# humidor_controller_v35.net
KiCad netlist of a schematic drawn in EAGLE
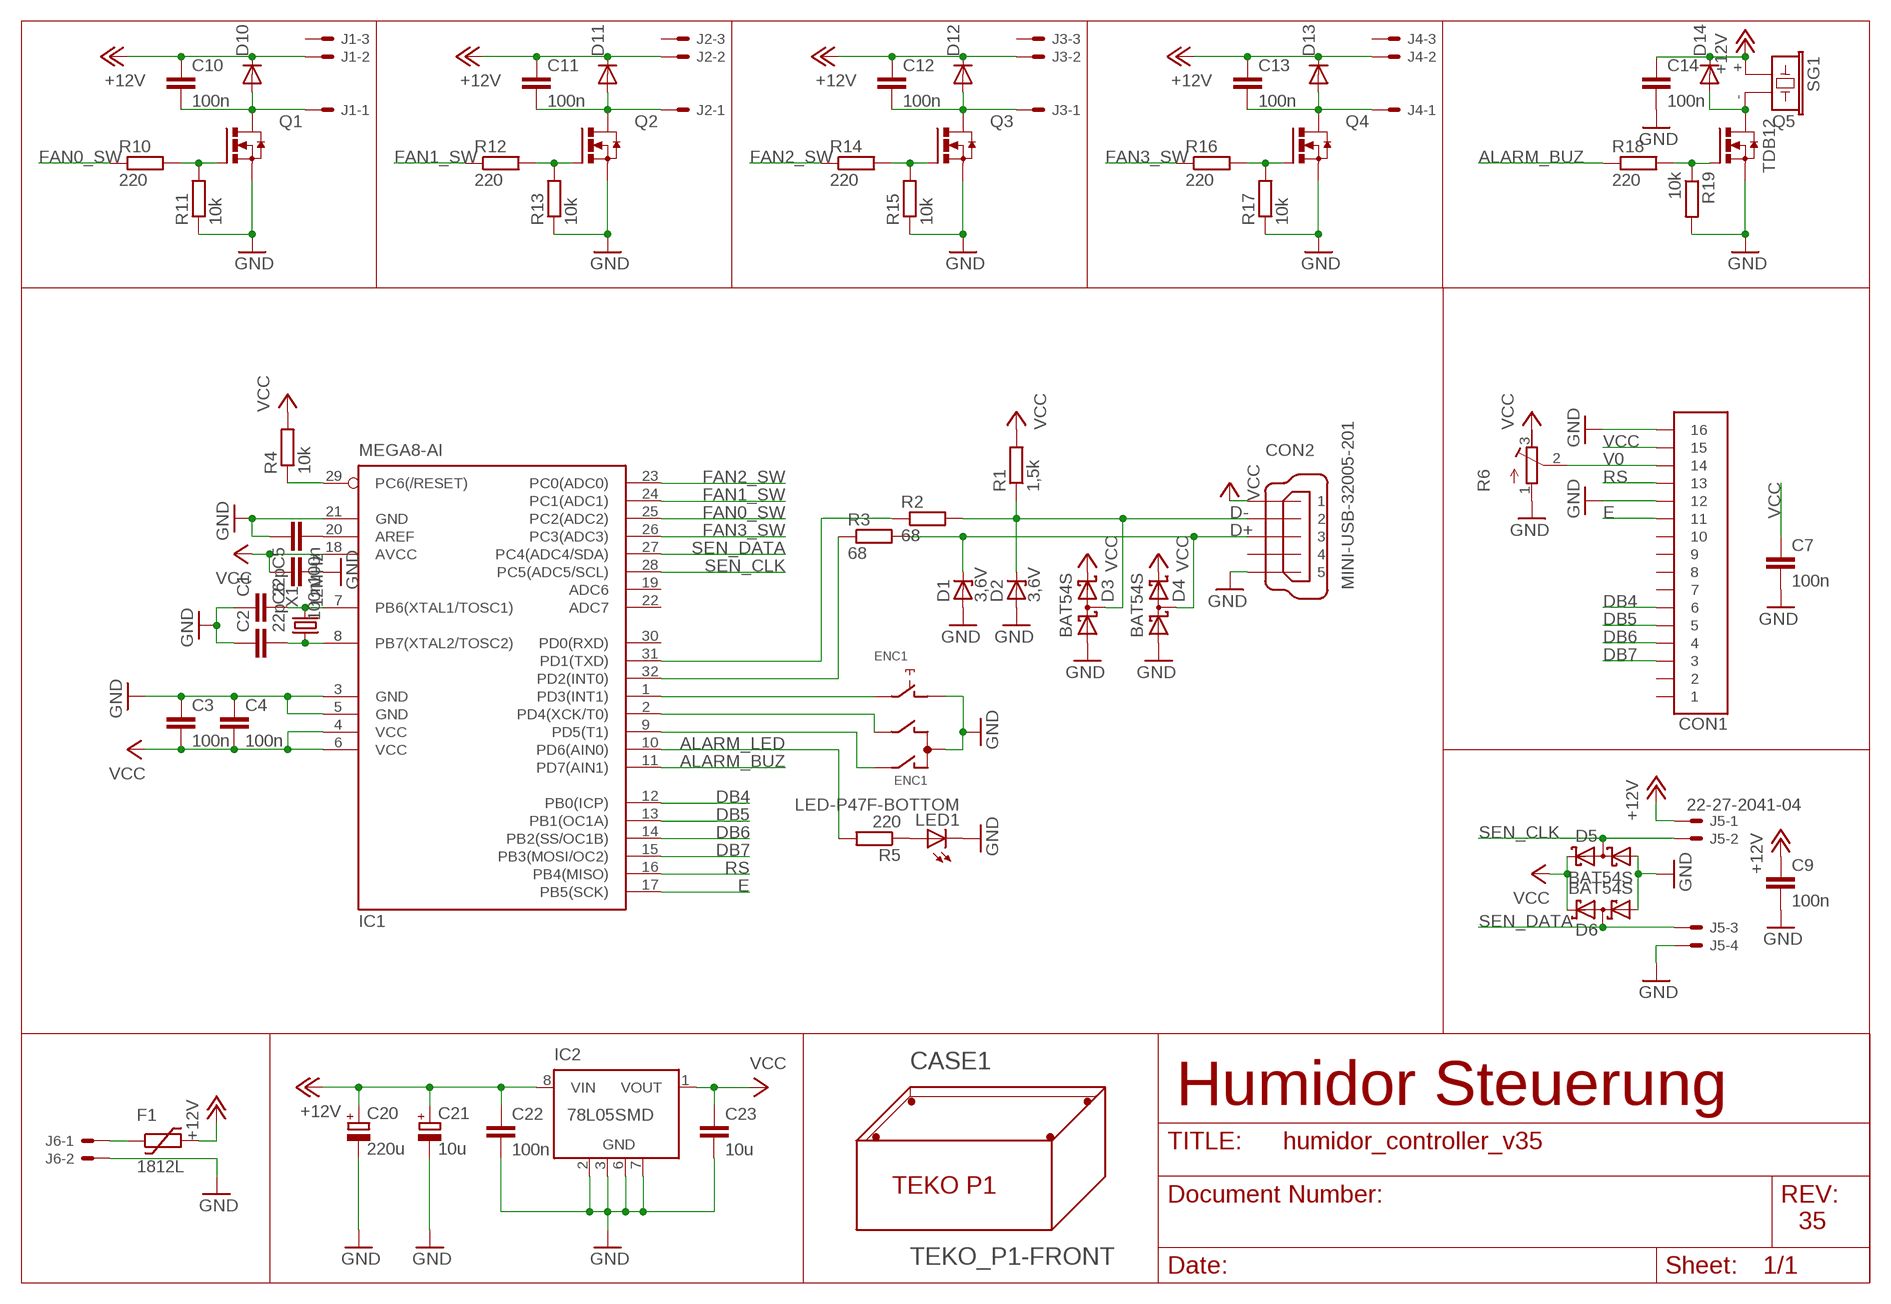
[diagram p0: schematic, sheet 1]

(export (version "E")
  (design (tool "Eeschema 10.0.6"))
  (components
    (comp (ref "C1")
      (value "22p")
      (footprint "eagle-import:C0805")
      (libsource (lib "eagle-import") (part "C-EUC0805"))
    )
    (comp (ref "C2")
      (value "22p")
      (footprint "eagle-import:C0805")
      (libsource (lib "eagle-import") (part "C-EUC0805"))
    )
    (comp (ref "C3")
      (value "100n")
      (footprint "eagle-import:C0805")
      (libsource (lib "eagle-import") (part "resistor_C-EUC0805"))
    )
    (comp (ref "C4")
      (value "100n")
      (footprint "eagle-import:C0805")
      (libsource (lib "eagle-import") (part "resistor_C-EUC0805"))
    )
    (comp (ref "C5")
      (value "100n")
      (footprint "eagle-import:C0805")
      (libsource (lib "eagle-import") (part "resistor_C-EUC0805"))
    )
    (comp (ref "C6")
      (value "100n")
      (footprint "eagle-import:C0805")
      (libsource (lib "eagle-import") (part "resistor_C-EUC0805"))
    )
    (comp (ref "C7")
      (value "100n")
      (footprint "eagle-import:C0805")
      (libsource (lib "eagle-import") (part "resistor_C-EUC0805"))
    )
    (comp (ref "C9")
      (value "100n")
      (footprint "eagle-import:C0805")
      (libsource (lib "eagle-import") (part "resistor_C-EUC0805"))
    )
    (comp (ref "C10")
      (value "100n")
      (footprint "eagle-import:C0805")
      (libsource (lib "eagle-import") (part "resistor_C-EUC0805"))
    )
    (comp (ref "C11")
      (value "100n")
      (footprint "eagle-import:C0805")
      (libsource (lib "eagle-import") (part "resistor_C-EUC0805"))
    )
    (comp (ref "C12")
      (value "100n")
      (footprint "eagle-import:C0805")
      (libsource (lib "eagle-import") (part "resistor_C-EUC0805"))
    )
    (comp (ref "C13")
      (value "100n")
      (footprint "eagle-import:C0805")
      (libsource (lib "eagle-import") (part "resistor_C-EUC0805"))
    )
    (comp (ref "C14")
      (value "100n")
      (footprint "eagle-import:C0805")
      (libsource (lib "eagle-import") (part "resistor_C-EUC0805"))
    )
    (comp (ref "C20")
      (value "220u")
      (footprint "eagle-import:PANASONIC_G")
      (libsource (lib "eagle-import") (part "CPOL-EUG"))
    )
    (comp (ref "C21")
      (value "10u")
      (footprint "eagle-import:PANASONIC_B")
      (libsource (lib "eagle-import") (part "CPOL-EUB"))
    )
    (comp (ref "C22")
      (value "100n")
      (footprint "eagle-import:C0805")
      (libsource (lib "eagle-import") (part "C-EUC0805"))
    )
    (comp (ref "C23")
      (value "10u")
      (footprint "eagle-import:C0805")
      (libsource (lib "eagle-import") (part "C-EUC0805"))
    )
    (comp (ref "CASE1")
      (value "TEKO_P1-FRONT")
      (footprint "eagle-import:TEKO_P1_FRONT")
      (libsource (lib "eagle-import") (part "TEKO_P1-FRONT"))
    )
    (comp (ref "CON1")
      (value "52207-16")
      (footprint "eagle-import:52207-16")
      (libsource (lib "eagle-import") (part "52207-16"))
    )
    (comp (ref "CON2")
      (value "MINI-USB-32005-201")
      (footprint "eagle-import:32005-201")
      (libsource (lib "eagle-import") (part "MINI-USB-32005-201"))
    )
    (comp (ref "D1")
      (value "3,6V")
      (footprint "eagle-import:SOD80C")
      (libsource (lib "eagle-import") (part "ZENER-DIODESOD80C"))
    )
    (comp (ref "D2")
      (value "3,6V")
      (footprint "eagle-import:SOD80C")
      (libsource (lib "eagle-import") (part "ZENER-DIODESOD80C"))
    )
    (comp (ref "D3")
      (value "BAT54S")
      (footprint "eagle-import:SOT23")
      (libsource (lib "eagle-import") (part "BAT54S"))
    )
    (comp (ref "D4")
      (value "BAT54S")
      (footprint "eagle-import:SOT23")
      (libsource (lib "eagle-import") (part "BAT54S"))
    )
    (comp (ref "D5")
      (value "BAT54S")
      (footprint "eagle-import:SOT23")
      (libsource (lib "eagle-import") (part "BAT54S"))
    )
    (comp (ref "D6")
      (value "BAT54S")
      (footprint "eagle-import:SOT23")
      (libsource (lib "eagle-import") (part "BAT54S"))
    )
    (comp (ref "D10")
      (value "DIODE-SOD123")
      (footprint "eagle-import:SOD123")
      (libsource (lib "eagle-import") (part "DIODE-SOD123"))
    )
    (comp (ref "D11")
      (value "DIODE-SOD123")
      (footprint "eagle-import:SOD123")
      (libsource (lib "eagle-import") (part "DIODE-SOD123"))
    )
    (comp (ref "D12")
      (value "DIODE-SOD123")
      (footprint "eagle-import:SOD123")
      (libsource (lib "eagle-import") (part "DIODE-SOD123"))
    )
    (comp (ref "D13")
      (value "DIODE-SOD123")
      (footprint "eagle-import:SOD123")
      (libsource (lib "eagle-import") (part "DIODE-SOD123"))
    )
    (comp (ref "D14")
      (value "DIODE-SOD123")
      (footprint "eagle-import:SOD123")
      (libsource (lib "eagle-import") (part "DIODE-SOD123"))
    )
    (comp (ref "ENC1")
      (value "NOBLE_RE0124")
      (footprint "eagle-import:RE0124")
      (libsource (lib "eagle-import") (part "NOBLE_RE0124"))
    )
    (comp (ref "F1")
      (value "1812L")
      (footprint "eagle-import:1812L")
      (libsource (lib "eagle-import") (part "1812L"))
    )
    (comp (ref "IC1")
      (value "MEGA8-AI")
      (footprint "eagle-import:TQFP32-08")
      (libsource (lib "eagle-import") (part "MEGA8-AI"))
    )
    (comp (ref "IC2")
      (value "78L05SMD")
      (footprint "eagle-import:SO08")
      (libsource (lib "eagle-import") (part "78LSMD05"))
    )
    (comp (ref "J1")
      (value "22-27-2031-03")
      (footprint "eagle-import:6410-03")
      (libsource (lib "eagle-import") (part "22-?-0327-2031"))
    )
    (comp (ref "J2")
      (value "22-27-2031-03")
      (footprint "eagle-import:6410-03")
      (libsource (lib "eagle-import") (part "22-?-0327-2031"))
    )
    (comp (ref "J3")
      (value "22-27-2031-03")
      (footprint "eagle-import:6410-03")
      (libsource (lib "eagle-import") (part "22-?-0327-2031"))
    )
    (comp (ref "J4")
      (value "22-27-2031-03")
      (footprint "eagle-import:6410-03")
      (libsource (lib "eagle-import") (part "22-?-0327-2031"))
    )
    (comp (ref "J5")
      (value "22-27-2041-04")
      (footprint "eagle-import:6410-04")
      (libsource (lib "eagle-import") (part "22-?-0427-2041"))
    )
    (comp (ref "J6")
      (value "22-27-2021-02")
      (footprint "eagle-import:6410-02")
      (libsource (lib "eagle-import") (part "22-?-0227-2021"))
    )
    (comp (ref "LED1")
      (value "LED-P47F-BOTTOM")
      (footprint "eagle-import:P47F-BOTTOM")
      (libsource (lib "eagle-import") (part "LED-P47F-BOTTOM"))
    )
    (comp (ref "Q1")
      (value "N-HEXFET_SOT23-IRLML2502")
      (footprint "eagle-import:SOT23")
      (libsource (lib "eagle-import") (part "N-HEXFET_?-SOT23IRLML2502"))
    )
    (comp (ref "Q2")
      (value "N-HEXFET_SOT23-IRLML2502")
      (footprint "eagle-import:SOT23")
      (libsource (lib "eagle-import") (part "N-HEXFET_?-SOT23IRLML2502"))
    )
    (comp (ref "Q3")
      (value "N-HEXFET_SOT23-IRLML2502")
      (footprint "eagle-import:SOT23")
      (libsource (lib "eagle-import") (part "N-HEXFET_?-SOT23IRLML2502"))
    )
    (comp (ref "Q4")
      (value "N-HEXFET_SOT23-IRLML2502")
      (footprint "eagle-import:SOT23")
      (libsource (lib "eagle-import") (part "N-HEXFET_?-SOT23IRLML2502"))
    )
    (comp (ref "Q5")
      (value "N-HEXFET_SOT23-IRLML2502")
      (footprint "eagle-import:SOT23")
      (libsource (lib "eagle-import") (part "N-HEXFET_?-SOT23IRLML2502"))
    )
    (comp (ref "R1")
      (value "1,5k")
      (footprint "eagle-import:R0805")
      (libsource (lib "eagle-import") (part "R-EU_R0805"))
    )
    (comp (ref "R2")
      (value "68")
      (footprint "eagle-import:R0805")
      (libsource (lib "eagle-import") (part "R-EU_R0805"))
    )
    (comp (ref "R3")
      (value "68")
      (footprint "eagle-import:R0805")
      (libsource (lib "eagle-import") (part "R-EU_R0805"))
    )
    (comp (ref "R4")
      (value "10k")
      (footprint "eagle-import:R0805")
      (libsource (lib "eagle-import") (part "R-EU_R0805"))
    )
    (comp (ref "R5")
      (value "220")
      (footprint "eagle-import:R0805")
      (libsource (lib "eagle-import") (part "R-EU_R0805"))
    )
    (comp (ref "R6")
      (value "R-TRIMM4G/J")
      (footprint "eagle-import:RTRIM4G_J")
      (libsource (lib "eagle-import") (part "R-TRIMM4G/J"))
    )
    (comp (ref "R10")
      (value "220")
      (footprint "eagle-import:R0805")
      (libsource (lib "eagle-import") (part "R-EU_R0805"))
    )
    (comp (ref "R11")
      (value "10k")
      (footprint "eagle-import:R0805")
      (libsource (lib "eagle-import") (part "R-EU_R0805"))
    )
    (comp (ref "R12")
      (value "220")
      (footprint "eagle-import:R0805")
      (libsource (lib "eagle-import") (part "R-EU_R0805"))
    )
    (comp (ref "R13")
      (value "10k")
      (footprint "eagle-import:R0805")
      (libsource (lib "eagle-import") (part "R-EU_R0805"))
    )
    (comp (ref "R14")
      (value "220")
      (footprint "eagle-import:R0805")
      (libsource (lib "eagle-import") (part "R-EU_R0805"))
    )
    (comp (ref "R15")
      (value "10k")
      (footprint "eagle-import:R0805")
      (libsource (lib "eagle-import") (part "R-EU_R0805"))
    )
    (comp (ref "R16")
      (value "220")
      (footprint "eagle-import:R0805")
      (libsource (lib "eagle-import") (part "R-EU_R0805"))
    )
    (comp (ref "R17")
      (value "10k")
      (footprint "eagle-import:R0805")
      (libsource (lib "eagle-import") (part "R-EU_R0805"))
    )
    (comp (ref "R18")
      (value "220")
      (footprint "eagle-import:R0805")
      (libsource (lib "eagle-import") (part "R-EU_R0805"))
    )
    (comp (ref "R19")
      (value "10k")
      (footprint "eagle-import:R0805")
      (libsource (lib "eagle-import") (part "R-EU_R0805"))
    )
    (comp (ref "SG1")
      (value "TDB12")
      (footprint "eagle-import:TDB")
      (libsource (lib "eagle-import") (part "TDB12"))
    )
    (comp (ref "X1")
      (value "12MHz")
      (footprint "eagle-import:HC49UP")
      (libsource (lib "eagle-import") (part "CRYSTALHC49UP"))
    )
  )
  (nets
    (net (code "1") (name "+12V") (class "Default")
      (node (ref "C10") (pin "1") (pinfunction "1_1") (pintype "passive"))
      (node (ref "C11") (pin "1") (pinfunction "1_1") (pintype "passive"))
      (node (ref "C12") (pin "1") (pinfunction "1_1") (pintype "passive"))
      (node (ref "C13") (pin "1") (pinfunction "1_1") (pintype "passive"))
      (node (ref "C14") (pin "1") (pinfunction "1_1") (pintype "passive"))
      (node (ref "C20") (pin "+") (pinfunction "+_+") (pintype "passive"))
      (node (ref "C21") (pin "+") (pinfunction "+_+") (pintype "passive"))
      (node (ref "C22") (pin "1") (pinfunction "1_1") (pintype "passive"))
      (node (ref "C9") (pin "1") (pinfunction "1_1") (pintype "passive"))
      (node (ref "D10") (pin "C") (pinfunction "C_C") (pintype "passive"))
      (node (ref "D11") (pin "C") (pinfunction "C_C") (pintype "passive"))
      (node (ref "D12") (pin "C") (pinfunction "C_C") (pintype "passive"))
      (node (ref "D13") (pin "C") (pinfunction "C_C") (pintype "passive"))
      (node (ref "D14") (pin "C") (pinfunction "C_C") (pintype "passive"))
      (node (ref "F1") (pin "P$2") (pinfunction "2_P$2") (pintype "passive"))
      (node (ref "IC2") (pin "8") (pinfunction "VIN_8") (pintype "passive"))
      (node (ref "J1") (pin "2") (pinfunction "S_2") (pintype "passive"))
      (node (ref "J2") (pin "2") (pinfunction "S_2") (pintype "passive"))
      (node (ref "J3") (pin "2") (pinfunction "S_2") (pintype "passive"))
      (node (ref "J4") (pin "2") (pinfunction "S_2") (pintype "passive"))
      (node (ref "J5") (pin "1") (pinfunction "S_1") (pintype "passive"))
      (node (ref "SG1") (pin "+") (pinfunction "1_+") (pintype "passive"))
    )
    (net (code "2") (name "/ALARM_BUZ") (class "Default")
      (node (ref "IC1") (pin "11") (pinfunction "PD7(AIN1)_11") (pintype "bidirectional"))
      (node (ref "R18") (pin "1") (pinfunction "1_1") (pintype "passive"))
    )
    (net (code "3") (name "/ALARM_LED") (class "Default")
      (node (ref "IC1") (pin "10") (pinfunction "PD6(AIN0)_10") (pintype "bidirectional"))
      (node (ref "R5") (pin "2") (pinfunction "2_2") (pintype "passive"))
    )
    (net (code "4") (name "/D+") (class "Default")
      (node (ref "CON2") (pin "3") (pinfunction "3_3") (pintype "passive"))
      (node (ref "D1") (pin "C") (pinfunction "C_C") (pintype "passive"))
      (node (ref "D4") (pin "3") (pinfunction "C1A2_3") (pintype "passive"))
      (node (ref "R3") (pin "2") (pinfunction "2_2") (pintype "passive"))
    )
    (net (code "5") (name "/D-") (class "Default")
      (node (ref "CON2") (pin "2") (pinfunction "2_2") (pintype "passive"))
      (node (ref "D2") (pin "C") (pinfunction "C_C") (pintype "passive"))
      (node (ref "D3") (pin "3") (pinfunction "C1A2_3") (pintype "passive"))
      (node (ref "R1") (pin "1") (pinfunction "1_1") (pintype "passive"))
      (node (ref "R2") (pin "2") (pinfunction "2_2") (pintype "passive"))
    )
    (net (code "6") (name "/DB4") (class "Default")
      (node (ref "CON1") (pin "6") (pinfunction "6_6") (pintype "bidirectional"))
      (node (ref "IC1") (pin "12") (pinfunction "PB0(ICP)_12") (pintype "bidirectional"))
    )
    (net (code "7") (name "/DB5") (class "Default")
      (node (ref "CON1") (pin "5") (pinfunction "5_5") (pintype "bidirectional"))
      (node (ref "IC1") (pin "13") (pinfunction "PB1(OC1A)_13") (pintype "bidirectional"))
    )
    (net (code "8") (name "/DB6") (class "Default")
      (node (ref "CON1") (pin "4") (pinfunction "4_4") (pintype "bidirectional"))
      (node (ref "IC1") (pin "14") (pinfunction "PB2(SS/OC1B)_14") (pintype "bidirectional"))
    )
    (net (code "9") (name "/DB7") (class "Default")
      (node (ref "CON1") (pin "3") (pinfunction "3_3") (pintype "bidirectional"))
      (node (ref "IC1") (pin "15") (pinfunction "PB3(MOSI/OC2)_15") (pintype "bidirectional"))
    )
    (net (code "10") (name "/E") (class "Default")
      (node (ref "CON1") (pin "11") (pinfunction "11_11") (pintype "bidirectional"))
      (node (ref "IC1") (pin "17") (pinfunction "PB5(SCK)_17") (pintype "bidirectional"))
    )
    (net (code "11") (name "/FAN0_SW") (class "Default")
      (node (ref "IC1") (pin "25") (pinfunction "PC2(ADC2)_25") (pintype "bidirectional"))
      (node (ref "R10") (pin "1") (pinfunction "1_1") (pintype "passive"))
    )
    (net (code "12") (name "/FAN1_SW") (class "Default")
      (node (ref "IC1") (pin "24") (pinfunction "PC1(ADC1)_24") (pintype "bidirectional"))
      (node (ref "R12") (pin "1") (pinfunction "1_1") (pintype "passive"))
    )
    (net (code "13") (name "/FAN2_SW") (class "Default")
      (node (ref "IC1") (pin "23") (pinfunction "PC0(ADC0)_23") (pintype "bidirectional"))
      (node (ref "R14") (pin "1") (pinfunction "1_1") (pintype "passive"))
    )
    (net (code "14") (name "/FAN3_SW") (class "Default")
      (node (ref "IC1") (pin "26") (pinfunction "PC3(ADC3)_26") (pintype "bidirectional"))
      (node (ref "R16") (pin "1") (pinfunction "1_1") (pintype "passive"))
    )
    (net (code "15") (name "/RS") (class "Default")
      (node (ref "CON1") (pin "13") (pinfunction "13_13") (pintype "bidirectional"))
      (node (ref "IC1") (pin "16") (pinfunction "PB4(MISO)_16") (pintype "bidirectional"))
    )
    (net (code "16") (name "/SEN_CLK") (class "Default")
      (node (ref "D5") (pin "3") (pinfunction "C1A2_3") (pintype "passive"))
      (node (ref "IC1") (pin "28") (pinfunction "PC5(ADC5/SCL)_28") (pintype "bidirectional"))
      (node (ref "J5") (pin "2") (pinfunction "S_2") (pintype "passive"))
    )
    (net (code "17") (name "/SEN_DATA") (class "Default")
      (node (ref "D6") (pin "3") (pinfunction "C1A2_3") (pintype "passive"))
      (node (ref "IC1") (pin "27") (pinfunction "PC4(ADC4/SDA)_27") (pintype "bidirectional"))
      (node (ref "J5") (pin "3") (pinfunction "S_3") (pintype "passive"))
    )
    (net (code "18") (name "/V0") (class "Default")
      (node (ref "CON1") (pin "14") (pinfunction "14_14") (pintype "bidirectional"))
      (node (ref "R6") (pin "2") (pinfunction "S_2") (pintype "passive"))
    )
    (net (code "19") (name "GND") (class "Default")
      (node (ref "C1") (pin "1") (pinfunction "1_1") (pintype "passive"))
      (node (ref "C14") (pin "2") (pinfunction "2_2") (pintype "passive"))
      (node (ref "C2") (pin "1") (pinfunction "1_1") (pintype "passive"))
      (node (ref "C20") (pin "-") (pinfunction "-_-") (pintype "passive"))
      (node (ref "C21") (pin "-") (pinfunction "-_-") (pintype "passive"))
      (node (ref "C22") (pin "2") (pinfunction "2_2") (pintype "passive"))
      (node (ref "C23") (pin "2") (pinfunction "2_2") (pintype "passive"))
      (node (ref "C3") (pin "1") (pinfunction "1_1") (pintype "passive"))
      (node (ref "C4") (pin "1") (pinfunction "1_1") (pintype "passive"))
      (node (ref "C5") (pin "1") (pinfunction "1_1") (pintype "passive"))
      (node (ref "C6") (pin "2") (pinfunction "2_2") (pintype "passive"))
      (node (ref "C7") (pin "2") (pinfunction "2_2") (pintype "passive"))
      (node (ref "C9") (pin "2") (pinfunction "2_2") (pintype "passive"))
      (node (ref "CON1") (pin "12") (pinfunction "12_12") (pintype "bidirectional"))
      (node (ref "CON1") (pin "16") (pinfunction "16_16") (pintype "bidirectional"))
      (node (ref "CON2") (pin "5") (pinfunction "5_5") (pintype "passive"))
      (node (ref "D1") (pin "A") (pinfunction "A_A") (pintype "passive"))
      (node (ref "D2") (pin "A") (pinfunction "A_A") (pintype "passive"))
      (node (ref "D3") (pin "1") (pinfunction "A1_1") (pintype "passive"))
      (node (ref "D4") (pin "1") (pinfunction "A1_1") (pintype "passive"))
      (node (ref "D5") (pin "1") (pinfunction "A1_1") (pintype "passive"))
      (node (ref "D6") (pin "1") (pinfunction "A1_1") (pintype "passive"))
      (node (ref "ENC1") (pin "+") (pinfunction "1_+") (pintype "passive"))
      (node (ref "ENC1") (pin "C") (pinfunction "C_C") (pintype "passive"))
      (node (ref "IC1") (pin "21") (pinfunction "GND_21") (pintype "power_in"))
      (node (ref "IC1") (pin "3") (pinfunction "GND_3") (pintype "power_in"))
      (node (ref "IC1") (pin "5") (pinfunction "GND_5") (pintype "power_in"))
      (node (ref "IC2") (pin "2") (pinfunction "GND_2") (pintype "power_in"))
      (node (ref "IC2") (pin "3") (pinfunction "GND_3") (pintype "power_in"))
      (node (ref "IC2") (pin "6") (pinfunction "GND_6") (pintype "power_in"))
      (node (ref "IC2") (pin "7") (pinfunction "GND_7") (pintype "power_in"))
      (node (ref "J5") (pin "4") (pinfunction "S_4") (pintype "passive"))
      (node (ref "J6") (pin "2") (pinfunction "S_2") (pintype "passive"))
      (node (ref "LED1") (pin "C") (pinfunction "C_C") (pintype "passive"))
      (node (ref "Q1") (pin "2") (pinfunction "S_2") (pintype "passive"))
      (node (ref "Q2") (pin "2") (pinfunction "S_2") (pintype "passive"))
      (node (ref "Q3") (pin "2") (pinfunction "S_2") (pintype "passive"))
      (node (ref "Q4") (pin "2") (pinfunction "S_2") (pintype "passive"))
      (node (ref "Q5") (pin "2") (pinfunction "S_2") (pintype "passive"))
      (node (ref "R11") (pin "1") (pinfunction "1_1") (pintype "passive"))
      (node (ref "R13") (pin "1") (pinfunction "1_1") (pintype "passive"))
      (node (ref "R15") (pin "1") (pinfunction "1_1") (pintype "passive"))
      (node (ref "R17") (pin "1") (pinfunction "1_1") (pintype "passive"))
      (node (ref "R19") (pin "2") (pinfunction "2_2") (pintype "passive"))
      (node (ref "R6") (pin "1") (pinfunction "E_1") (pintype "passive"))
    )
    (net (code "20") (name "Net-(ENC1B-2)") (class "Default")
      (node (ref "ENC1") (pin "-") (pinfunction "2_-") (pintype "passive"))
      (node (ref "IC1") (pin "1") (pinfunction "PD3(INT1)_1") (pintype "bidirectional"))
    )
    (net (code "21") (name "Net-(F1-1)") (class "Default")
      (node (ref "F1") (pin "P$1") (pinfunction "1_P$1") (pintype "passive"))
      (node (ref "J6") (pin "1") (pinfunction "S_1") (pintype "passive"))
    )
    (net (code "22") (name "Net-(IC1-AREF)") (class "Default")
      (node (ref "C5") (pin "2") (pinfunction "2_2") (pintype "passive"))
      (node (ref "IC1") (pin "20") (pinfunction "AREF_20") (pintype "passive"))
    )
    (net (code "23") (name "Net-(IC1-PB6(XTAL1{slash}TOSC1))") (class "Default")
      (node (ref "C1") (pin "2") (pinfunction "2_2") (pintype "passive"))
      (node (ref "IC1") (pin "7") (pinfunction "PB6(XTAL1/TOSC1)_7") (pintype "bidirectional"))
      (node (ref "X1") (pin "2") (pinfunction "2_2") (pintype "passive"))
    )
    (net (code "24") (name "Net-(IC1-PB7(XTAL2{slash}TOSC2))") (class "Default")
      (node (ref "C2") (pin "2") (pinfunction "2_2") (pintype "passive"))
      (node (ref "IC1") (pin "8") (pinfunction "PB7(XTAL2/TOSC2)_8") (pintype "bidirectional"))
      (node (ref "X1") (pin "1") (pinfunction "1_1") (pintype "passive"))
    )
    (net (code "25") (name "Net-(IC1-PC6({slash}RESET))") (class "Default")
      (node (ref "IC1") (pin "29") (pinfunction "PC6(/RESET)_29") (pintype "bidirectional"))
      (node (ref "R4") (pin "1") (pinfunction "1_1") (pintype "passive"))
    )
    (net (code "26") (name "Net-(IC1-PD1(TXD))") (class "Default")
      (node (ref "IC1") (pin "31") (pinfunction "PD1(TXD)_31") (pintype "bidirectional"))
      (node (ref "R2") (pin "1") (pinfunction "1_1") (pintype "passive"))
    )
    (net (code "27") (name "Net-(IC1-PD2(INT0))") (class "Default")
      (node (ref "IC1") (pin "32") (pinfunction "PD2(INT0)_32") (pintype "bidirectional"))
      (node (ref "R3") (pin "1") (pinfunction "1_1") (pintype "passive"))
    )
    (net (code "28") (name "Net-(IC1-PD4(XCK{slash}T0))") (class "Default")
      (node (ref "ENC1") (pin "B") (pinfunction "B_B") (pintype "passive"))
      (node (ref "IC1") (pin "2") (pinfunction "PD4(XCK/T0)_2") (pintype "bidirectional"))
    )
    (net (code "29") (name "Net-(IC1-PD5(T1))") (class "Default")
      (node (ref "ENC1") (pin "A") (pinfunction "A_A") (pintype "passive"))
      (node (ref "IC1") (pin "9") (pinfunction "PD5(T1)_9") (pintype "bidirectional"))
    )
    (net (code "30") (name "Net-(J1A-S)") (class "Default")
      (node (ref "C10") (pin "2") (pinfunction "2_2") (pintype "passive"))
      (node (ref "D10") (pin "A") (pinfunction "A_A") (pintype "passive"))
      (node (ref "J1") (pin "1") (pinfunction "S_1") (pintype "passive"))
      (node (ref "Q1") (pin "3") (pinfunction "D_3") (pintype "passive"))
    )
    (net (code "31") (name "Net-(J2A-S)") (class "Default")
      (node (ref "C11") (pin "2") (pinfunction "2_2") (pintype "passive"))
      (node (ref "D11") (pin "A") (pinfunction "A_A") (pintype "passive"))
      (node (ref "J2") (pin "1") (pinfunction "S_1") (pintype "passive"))
      (node (ref "Q2") (pin "3") (pinfunction "D_3") (pintype "passive"))
    )
    (net (code "32") (name "Net-(J3A-S)") (class "Default")
      (node (ref "C12") (pin "2") (pinfunction "2_2") (pintype "passive"))
      (node (ref "D12") (pin "A") (pinfunction "A_A") (pintype "passive"))
      (node (ref "J3") (pin "1") (pinfunction "S_1") (pintype "passive"))
      (node (ref "Q3") (pin "3") (pinfunction "D_3") (pintype "passive"))
    )
    (net (code "33") (name "Net-(J4A-S)") (class "Default")
      (node (ref "C13") (pin "2") (pinfunction "2_2") (pintype "passive"))
      (node (ref "D13") (pin "A") (pinfunction "A_A") (pintype "passive"))
      (node (ref "J4") (pin "1") (pinfunction "S_1") (pintype "passive"))
      (node (ref "Q4") (pin "3") (pinfunction "D_3") (pintype "passive"))
    )
    (net (code "34") (name "Net-(LED1-PadA)") (class "Default")
      (node (ref "LED1") (pin "A") (pinfunction "A_A") (pintype "passive"))
      (node (ref "R5") (pin "1") (pinfunction "1_1") (pintype "passive"))
    )
    (net (code "35") (name "Net-(Q1-G)") (class "Default")
      (node (ref "Q1") (pin "1") (pinfunction "G_1") (pintype "passive"))
      (node (ref "R10") (pin "2") (pinfunction "2_2") (pintype "passive"))
      (node (ref "R11") (pin "2") (pinfunction "2_2") (pintype "passive"))
    )
    (net (code "36") (name "Net-(Q2-G)") (class "Default")
      (node (ref "Q2") (pin "1") (pinfunction "G_1") (pintype "passive"))
      (node (ref "R12") (pin "2") (pinfunction "2_2") (pintype "passive"))
      (node (ref "R13") (pin "2") (pinfunction "2_2") (pintype "passive"))
    )
    (net (code "37") (name "Net-(Q3-G)") (class "Default")
      (node (ref "Q3") (pin "1") (pinfunction "G_1") (pintype "passive"))
      (node (ref "R14") (pin "2") (pinfunction "2_2") (pintype "passive"))
      (node (ref "R15") (pin "2") (pinfunction "2_2") (pintype "passive"))
    )
    (net (code "38") (name "Net-(Q4-G)") (class "Default")
      (node (ref "Q4") (pin "1") (pinfunction "G_1") (pintype "passive"))
      (node (ref "R16") (pin "2") (pinfunction "2_2") (pintype "passive"))
      (node (ref "R17") (pin "2") (pinfunction "2_2") (pintype "passive"))
    )
    (net (code "39") (name "Net-(Q5-D)") (class "Default")
      (node (ref "D14") (pin "A") (pinfunction "A_A") (pintype "passive"))
      (node (ref "Q5") (pin "3") (pinfunction "D_3") (pintype "passive"))
      (node (ref "SG1") (pin "-") (pinfunction "2_-") (pintype "passive"))
    )
    (net (code "40") (name "Net-(Q5-G)") (class "Default")
      (node (ref "Q5") (pin "1") (pinfunction "G_1") (pintype "passive"))
      (node (ref "R18") (pin "2") (pinfunction "2_2") (pintype "passive"))
      (node (ref "R19") (pin "1") (pinfunction "1_1") (pintype "passive"))
    )
    (net (code "41") (name "VCC") (class "Default")
      (node (ref "C23") (pin "1") (pinfunction "1_1") (pintype "passive"))
      (node (ref "C3") (pin "2") (pinfunction "2_2") (pintype "passive"))
      (node (ref "C4") (pin "2") (pinfunction "2_2") (pintype "passive"))
      (node (ref "C6") (pin "1") (pinfunction "1_1") (pintype "passive"))
      (node (ref "C7") (pin "1") (pinfunction "1_1") (pintype "passive"))
      (node (ref "CON1") (pin "15") (pinfunction "15_15") (pintype "bidirectional"))
      (node (ref "CON2") (pin "1") (pinfunction "1_1") (pintype "passive"))
      (node (ref "D3") (pin "2") (pinfunction "C2_2") (pintype "passive"))
      (node (ref "D4") (pin "2") (pinfunction "C2_2") (pintype "passive"))
      (node (ref "D5") (pin "2") (pinfunction "C2_2") (pintype "passive"))
      (node (ref "D6") (pin "2") (pinfunction "C2_2") (pintype "passive"))
      (node (ref "IC1") (pin "18") (pinfunction "AVCC_18") (pintype "power_in"))
      (node (ref "IC1") (pin "4") (pinfunction "VCC_4") (pintype "power_in"))
      (node (ref "IC1") (pin "6") (pinfunction "VCC_6") (pintype "power_in"))
      (node (ref "IC2") (pin "1") (pinfunction "VOUT_1") (pintype "output"))
      (node (ref "R1") (pin "2") (pinfunction "2_2") (pintype "passive"))
      (node (ref "R4") (pin "2") (pinfunction "2_2") (pintype "passive"))
      (node (ref "R6") (pin "3") (pinfunction "A_3") (pintype "passive"))
    )
    (net (code "42") (name "unconnected-(CON1-Pad1)") (class "Default")
      (node (ref "CON1") (pin "1") (pinfunction "1_1") (pintype "bidirectional"))
    )
    (net (code "43") (name "unconnected-(CON1-Pad2)") (class "Default")
      (node (ref "CON1") (pin "2") (pinfunction "2_2") (pintype "bidirectional"))
    )
    (net (code "44") (name "unconnected-(CON1-Pad7)") (class "Default")
      (node (ref "CON1") (pin "7") (pinfunction "7_7") (pintype "bidirectional"))
    )
    (net (code "45") (name "unconnected-(CON1-Pad8)") (class "Default")
      (node (ref "CON1") (pin "8") (pinfunction "8_8") (pintype "bidirectional"))
    )
    (net (code "46") (name "unconnected-(CON1-Pad9)") (class "Default")
      (node (ref "CON1") (pin "9") (pinfunction "9_9") (pintype "bidirectional"))
    )
    (net (code "47") (name "unconnected-(CON1-Pad10)") (class "Default")
      (node (ref "CON1") (pin "10") (pinfunction "10_10") (pintype "bidirectional"))
    )
    (net (code "48") (name "unconnected-(CON2-Pad4)") (class "Default")
      (node (ref "CON2") (pin "4") (pinfunction "4_4") (pintype "passive"))
    )
    (net (code "49") (name "unconnected-(IC1-ADC6-Pad19)") (class "Default")
      (node (ref "IC1") (pin "19") (pinfunction "ADC6_19") (pintype "bidirectional"))
    )
    (net (code "50") (name "unconnected-(IC1-ADC7-Pad22)") (class "Default")
      (node (ref "IC1") (pin "22") (pinfunction "ADC7_22") (pintype "bidirectional"))
    )
    (net (code "51") (name "unconnected-(IC1-PD0(RXD)-Pad30)") (class "Default")
      (node (ref "IC1") (pin "30") (pinfunction "PD0(RXD)_30") (pintype "bidirectional"))
    )
    (net (code "52") (name "unconnected-(J1C-S-Pad3)") (class "Default")
      (node (ref "J1") (pin "3") (pinfunction "S_3") (pintype "passive"))
    )
    (net (code "53") (name "unconnected-(J2C-S-Pad3)") (class "Default")
      (node (ref "J2") (pin "3") (pinfunction "S_3") (pintype "passive"))
    )
    (net (code "54") (name "unconnected-(J3C-S-Pad3)") (class "Default")
      (node (ref "J3") (pin "3") (pinfunction "S_3") (pintype "passive"))
    )
    (net (code "55") (name "unconnected-(J4C-S-Pad3)") (class "Default")
      (node (ref "J4") (pin "3") (pinfunction "S_3") (pintype "passive"))
    )
  )
)
